# DINRELAY8.net
KiCad netlist of a schematic drawn in EAGLE
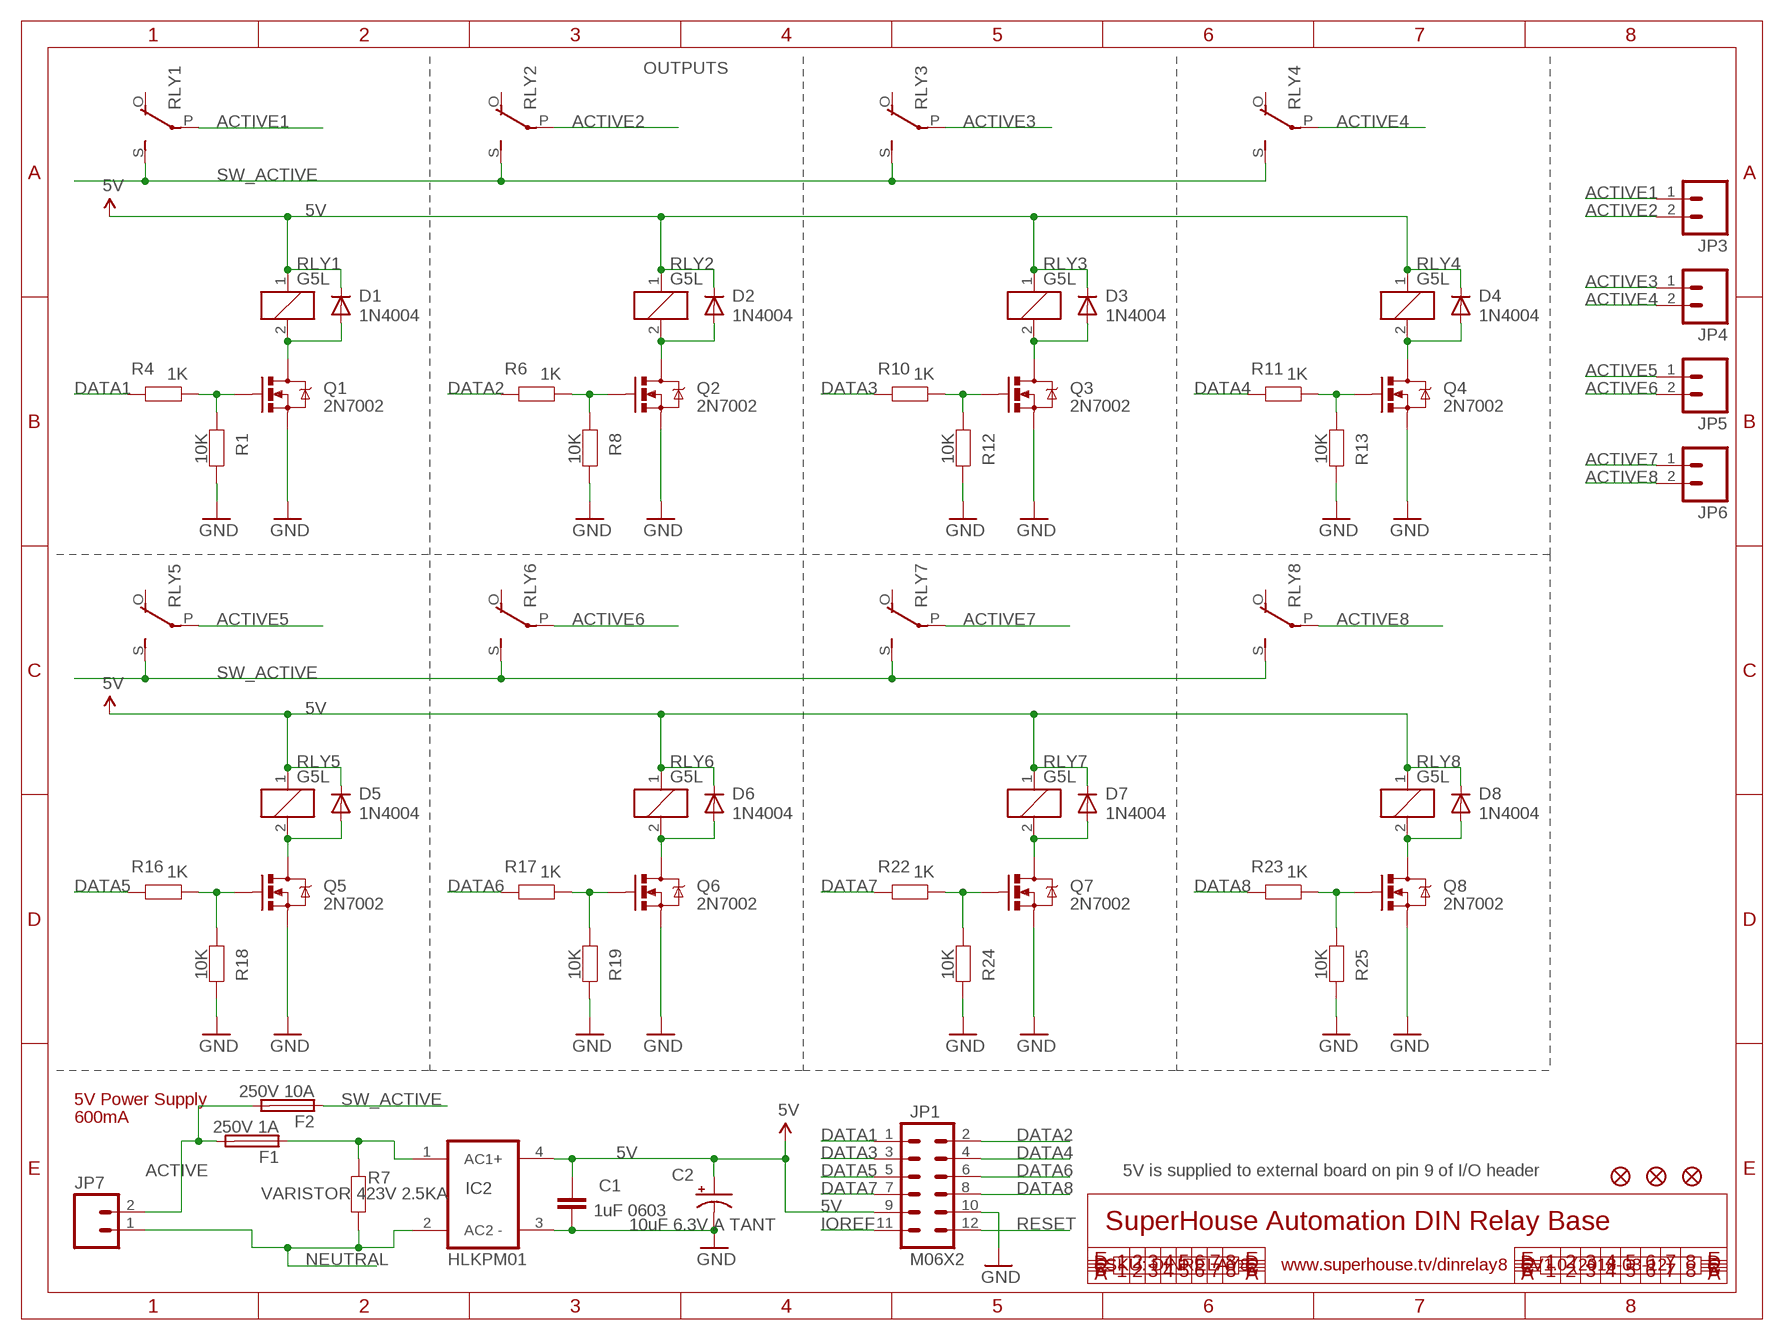
[diagram p0: schematic, sheet 1]

(export (version "E")
  (design (tool "Eeschema 10.0.6"))
  (components
    (comp (ref "C1")
      (value "1uF 0603")
      (footprint "eagle-import:0603@1")
      (libsource (lib "eagle-import") (part "CAP0603"))
    )
    (comp (ref "C2")
      (value "10uF 6.3V A TANT")
      (footprint "eagle-import:EIA3216")
      (libsource (lib "eagle-import") (part "CAP_POL1206"))
    )
    (comp (ref "D1")
      (value "1N4004")
      (footprint "eagle-import:SMB-DIODE")
      (libsource (lib "eagle-import") (part "DIODESMB"))
    )
    (comp (ref "D2")
      (value "1N4004")
      (footprint "eagle-import:SMB-DIODE")
      (libsource (lib "eagle-import") (part "DIODESMB"))
    )
    (comp (ref "D3")
      (value "1N4004")
      (footprint "eagle-import:SMB-DIODE")
      (libsource (lib "eagle-import") (part "DIODESMB"))
    )
    (comp (ref "D4")
      (value "1N4004")
      (footprint "eagle-import:SMB-DIODE")
      (libsource (lib "eagle-import") (part "DIODESMB"))
    )
    (comp (ref "D5")
      (value "1N4004")
      (footprint "eagle-import:SMB-DIODE")
      (libsource (lib "eagle-import") (part "DIODESMB"))
    )
    (comp (ref "D6")
      (value "1N4004")
      (footprint "eagle-import:SMB-DIODE")
      (libsource (lib "eagle-import") (part "DIODESMB"))
    )
    (comp (ref "D7")
      (value "1N4004")
      (footprint "eagle-import:SMB-DIODE")
      (libsource (lib "eagle-import") (part "DIODESMB"))
    )
    (comp (ref "D8")
      (value "1N4004")
      (footprint "eagle-import:SMB-DIODE")
      (libsource (lib "eagle-import") (part "DIODESMB"))
    )
    (comp (ref "F1")
      (value "250V 1A")
      (footprint "eagle-import:PICOFUSE")
      (libsource (lib "eagle-import") (part "PICOFUSEH"))
    )
    (comp (ref "F2")
      (value "250V 10A")
      (footprint "eagle-import:PICOFUSE")
      (libsource (lib "eagle-import") (part "PICOFUSEH"))
    )
    (comp (ref "FID1")
      (value "FIDUCIAL1X2.5")
      (footprint "eagle-import:FIDUCIAL-1X2.5")
      (libsource (lib "eagle-import") (part "FIDUCIAL1X2.5"))
    )
    (comp (ref "FID2")
      (value "FIDUCIAL1X2.5")
      (footprint "eagle-import:FIDUCIAL-1X2.5")
      (libsource (lib "eagle-import") (part "FIDUCIAL1X2.5"))
    )
    (comp (ref "FID3")
      (value "FIDUCIAL1X2.5")
      (footprint "eagle-import:FIDUCIAL-1X2.5")
      (libsource (lib "eagle-import") (part "FIDUCIAL1X2.5"))
    )
    (comp (ref "IC2")
      (value "HLKPM01")
      (footprint "eagle-import:HLKPM01")
      (libsource (lib "eagle-import") (part "HLKPM01"))
    )
    (comp (ref "JP1")
      (value "M06X2")
      (footprint "eagle-import:2X6-SHROUDED")
      (libsource (lib "eagle-import") (part "M06X2"))
    )
    (comp (ref "JP3")
      (value "M025MM")
      (footprint "eagle-import:SCREWTERMINAL-5MM-2")
      (libsource (lib "eagle-import") (part "M025MM"))
    )
    (comp (ref "JP4")
      (value "M025MM")
      (footprint "eagle-import:SCREWTERMINAL-5MM-2")
      (libsource (lib "eagle-import") (part "M025MM"))
    )
    (comp (ref "JP5")
      (value "M025MM")
      (footprint "eagle-import:SCREWTERMINAL-5MM-2")
      (libsource (lib "eagle-import") (part "M025MM"))
    )
    (comp (ref "JP6")
      (value "M025MM")
      (footprint "eagle-import:SCREWTERMINAL-5MM-2")
      (libsource (lib "eagle-import") (part "M025MM"))
    )
    (comp (ref "JP7")
      (value "M025MM")
      (footprint "eagle-import:SCREWTERMINAL-5MM-2")
      (libsource (lib "eagle-import") (part "M025MM"))
    )
    (comp (ref "Q1")
      (value "2N7002")
      (footprint "eagle-import:SOT23-3")
      (libsource (lib "eagle-import") (part "MOSFET-NCHANNELSMD"))
    )
    (comp (ref "Q2")
      (value "2N7002")
      (footprint "eagle-import:SOT23-3")
      (libsource (lib "eagle-import") (part "MOSFET-NCHANNELSMD"))
    )
    (comp (ref "Q3")
      (value "2N7002")
      (footprint "eagle-import:SOT23-3")
      (libsource (lib "eagle-import") (part "MOSFET-NCHANNELSMD"))
    )
    (comp (ref "Q4")
      (value "2N7002")
      (footprint "eagle-import:SOT23-3")
      (libsource (lib "eagle-import") (part "MOSFET-NCHANNELSMD"))
    )
    (comp (ref "Q5")
      (value "2N7002")
      (footprint "eagle-import:SOT23-3")
      (libsource (lib "eagle-import") (part "MOSFET-NCHANNELSMD"))
    )
    (comp (ref "Q6")
      (value "2N7002")
      (footprint "eagle-import:SOT23-3")
      (libsource (lib "eagle-import") (part "MOSFET-NCHANNELSMD"))
    )
    (comp (ref "Q7")
      (value "2N7002")
      (footprint "eagle-import:SOT23-3")
      (libsource (lib "eagle-import") (part "MOSFET-NCHANNELSMD"))
    )
    (comp (ref "Q8")
      (value "2N7002")
      (footprint "eagle-import:SOT23-3")
      (libsource (lib "eagle-import") (part "MOSFET-NCHANNELSMD"))
    )
    (comp (ref "R1")
      (value "10K")
      (footprint "eagle-import:0603")
      (libsource (lib "eagle-import") (part "RESISTOR0603"))
    )
    (comp (ref "R4")
      (value "1K")
      (footprint "eagle-import:0603")
      (libsource (lib "eagle-import") (part "RESISTOR0603"))
    )
    (comp (ref "R6")
      (value "1K")
      (footprint "eagle-import:0603")
      (libsource (lib "eagle-import") (part "RESISTOR0603"))
    )
    (comp (ref "R7")
      (value "VARISTOR 423V 2.5KA")
      (footprint "eagle-import:AXIAL-0.3")
      (libsource (lib "eagle-import") (part "freetronics-master-v1.1_RESISTORPTH1"))
    )
    (comp (ref "R8")
      (value "10K")
      (footprint "eagle-import:0603")
      (libsource (lib "eagle-import") (part "RESISTOR0603"))
    )
    (comp (ref "R10")
      (value "1K")
      (footprint "eagle-import:0603")
      (libsource (lib "eagle-import") (part "RESISTOR0603"))
    )
    (comp (ref "R11")
      (value "1K")
      (footprint "eagle-import:0603")
      (libsource (lib "eagle-import") (part "RESISTOR0603"))
    )
    (comp (ref "R12")
      (value "10K")
      (footprint "eagle-import:0603")
      (libsource (lib "eagle-import") (part "RESISTOR0603"))
    )
    (comp (ref "R13")
      (value "10K")
      (footprint "eagle-import:0603")
      (libsource (lib "eagle-import") (part "RESISTOR0603"))
    )
    (comp (ref "R16")
      (value "1K")
      (footprint "eagle-import:0603")
      (libsource (lib "eagle-import") (part "RESISTOR0603"))
    )
    (comp (ref "R17")
      (value "1K")
      (footprint "eagle-import:0603")
      (libsource (lib "eagle-import") (part "RESISTOR0603"))
    )
    (comp (ref "R18")
      (value "10K")
      (footprint "eagle-import:0603")
      (libsource (lib "eagle-import") (part "RESISTOR0603"))
    )
    (comp (ref "R19")
      (value "10K")
      (footprint "eagle-import:0603")
      (libsource (lib "eagle-import") (part "RESISTOR0603"))
    )
    (comp (ref "R22")
      (value "1K")
      (footprint "eagle-import:0603")
      (libsource (lib "eagle-import") (part "RESISTOR0603"))
    )
    (comp (ref "R23")
      (value "1K")
      (footprint "eagle-import:0603")
      (libsource (lib "eagle-import") (part "RESISTOR0603"))
    )
    (comp (ref "R24")
      (value "10K")
      (footprint "eagle-import:0603")
      (libsource (lib "eagle-import") (part "RESISTOR0603"))
    )
    (comp (ref "R25")
      (value "10K")
      (footprint "eagle-import:0603")
      (libsource (lib "eagle-import") (part "RESISTOR0603"))
    )
    (comp (ref "RLY1")
      (value "G5L")
      (footprint "eagle-import:G5LE")
      (libsource (lib "eagle-import") (part "G5L"))
    )
    (comp (ref "RLY2")
      (value "G5L")
      (footprint "eagle-import:G5LE")
      (libsource (lib "eagle-import") (part "G5L"))
    )
    (comp (ref "RLY3")
      (value "G5L")
      (footprint "eagle-import:G5LE")
      (libsource (lib "eagle-import") (part "G5L"))
    )
    (comp (ref "RLY4")
      (value "G5L")
      (footprint "eagle-import:G5LE")
      (libsource (lib "eagle-import") (part "G5L"))
    )
    (comp (ref "RLY5")
      (value "G5L")
      (footprint "eagle-import:G5LE")
      (libsource (lib "eagle-import") (part "G5L"))
    )
    (comp (ref "RLY6")
      (value "G5L")
      (footprint "eagle-import:G5LE")
      (libsource (lib "eagle-import") (part "G5L"))
    )
    (comp (ref "RLY7")
      (value "G5L")
      (footprint "eagle-import:G5LE")
      (libsource (lib "eagle-import") (part "G5L"))
    )
    (comp (ref "RLY8")
      (value "G5L")
      (footprint "eagle-import:G5LE")
      (libsource (lib "eagle-import") (part "G5L"))
    )
  )
  (nets
    (net (code "1") (name "/ACTIVE") (class "Default")
      (node (ref "F1") (pin "2") (pinfunction "2_2") (pintype "passive"))
      (node (ref "F2") (pin "2") (pinfunction "2_2") (pintype "passive"))
      (node (ref "JP7") (pin "2") (pinfunction "2_2") (pintype "passive"))
    )
    (net (code "2") (name "/ACTIVE1") (class "Default")
      (node (ref "JP3") (pin "1") (pinfunction "1_1") (pintype "passive"))
      (node (ref "RLY1") (pin "P") (pinfunction "P_P") (pintype "passive"))
    )
    (net (code "3") (name "/ACTIVE2") (class "Default")
      (node (ref "JP3") (pin "2") (pinfunction "2_2") (pintype "passive"))
      (node (ref "RLY2") (pin "P") (pinfunction "P_P") (pintype "passive"))
    )
    (net (code "4") (name "/ACTIVE3") (class "Default")
      (node (ref "JP4") (pin "1") (pinfunction "1_1") (pintype "passive"))
      (node (ref "RLY3") (pin "P") (pinfunction "P_P") (pintype "passive"))
    )
    (net (code "5") (name "/ACTIVE4") (class "Default")
      (node (ref "JP4") (pin "2") (pinfunction "2_2") (pintype "passive"))
      (node (ref "RLY4") (pin "P") (pinfunction "P_P") (pintype "passive"))
    )
    (net (code "6") (name "/ACTIVE5") (class "Default")
      (node (ref "JP5") (pin "1") (pinfunction "1_1") (pintype "passive"))
      (node (ref "RLY5") (pin "P") (pinfunction "P_P") (pintype "passive"))
    )
    (net (code "7") (name "/ACTIVE6") (class "Default")
      (node (ref "JP5") (pin "2") (pinfunction "2_2") (pintype "passive"))
      (node (ref "RLY6") (pin "P") (pinfunction "P_P") (pintype "passive"))
    )
    (net (code "8") (name "/ACTIVE7") (class "Default")
      (node (ref "JP6") (pin "1") (pinfunction "1_1") (pintype "passive"))
      (node (ref "RLY7") (pin "P") (pinfunction "P_P") (pintype "passive"))
    )
    (net (code "9") (name "/ACTIVE8") (class "Default")
      (node (ref "JP6") (pin "2") (pinfunction "2_2") (pintype "passive"))
      (node (ref "RLY8") (pin "P") (pinfunction "P_P") (pintype "passive"))
    )
    (net (code "10") (name "/DATA1") (class "Default")
      (node (ref "JP1") (pin "1") (pinfunction "1_1") (pintype "passive"))
      (node (ref "R4") (pin "2") (pinfunction "2_2") (pintype "passive"))
    )
    (net (code "11") (name "/DATA2") (class "Default")
      (node (ref "JP1") (pin "2") (pinfunction "2_2") (pintype "passive"))
      (node (ref "R6") (pin "2") (pinfunction "2_2") (pintype "passive"))
    )
    (net (code "12") (name "/DATA3") (class "Default")
      (node (ref "JP1") (pin "3") (pinfunction "3_3") (pintype "passive"))
      (node (ref "R10") (pin "2") (pinfunction "2_2") (pintype "passive"))
    )
    (net (code "13") (name "/DATA4") (class "Default")
      (node (ref "JP1") (pin "4") (pinfunction "4_4") (pintype "passive"))
      (node (ref "R11") (pin "2") (pinfunction "2_2") (pintype "passive"))
    )
    (net (code "14") (name "/DATA5") (class "Default")
      (node (ref "JP1") (pin "5") (pinfunction "5_5") (pintype "passive"))
      (node (ref "R16") (pin "2") (pinfunction "2_2") (pintype "passive"))
    )
    (net (code "15") (name "/DATA6") (class "Default")
      (node (ref "JP1") (pin "6") (pinfunction "6_6") (pintype "passive"))
      (node (ref "R17") (pin "2") (pinfunction "2_2") (pintype "passive"))
    )
    (net (code "16") (name "/DATA7") (class "Default")
      (node (ref "JP1") (pin "7") (pinfunction "7_7") (pintype "passive"))
      (node (ref "R22") (pin "2") (pinfunction "2_2") (pintype "passive"))
    )
    (net (code "17") (name "/DATA8") (class "Default")
      (node (ref "JP1") (pin "8") (pinfunction "8_8") (pintype "passive"))
      (node (ref "R23") (pin "2") (pinfunction "2_2") (pintype "passive"))
    )
    (net (code "18") (name "/IOREF") (class "Default")
      (node (ref "JP1") (pin "11") (pinfunction "11_11") (pintype "passive"))
    )
    (net (code "19") (name "/NEUTRAL") (class "Default")
      (node (ref "IC2") (pin "2") (pinfunction "AC2_2") (pintype "bidirectional"))
      (node (ref "JP7") (pin "1") (pinfunction "1_1") (pintype "passive"))
      (node (ref "R7") (pin "P$1") (pinfunction "1_P$1") (pintype "passive"))
    )
    (net (code "20") (name "/RESET") (class "Default")
      (node (ref "JP1") (pin "12") (pinfunction "12_12") (pintype "passive"))
    )
    (net (code "21") (name "/SW_ACTIVE") (class "Default")
      (node (ref "F2") (pin "1") (pinfunction "1_1") (pintype "passive"))
      (node (ref "RLY1") (pin "S") (pinfunction "S_S") (pintype "passive"))
      (node (ref "RLY2") (pin "S") (pinfunction "S_S") (pintype "passive"))
      (node (ref "RLY3") (pin "S") (pinfunction "S_S") (pintype "passive"))
      (node (ref "RLY4") (pin "S") (pinfunction "S_S") (pintype "passive"))
      (node (ref "RLY5") (pin "S") (pinfunction "S_S") (pintype "passive"))
      (node (ref "RLY6") (pin "S") (pinfunction "S_S") (pintype "passive"))
      (node (ref "RLY7") (pin "S") (pinfunction "S_S") (pintype "passive"))
      (node (ref "RLY8") (pin "S") (pinfunction "S_S") (pintype "passive"))
    )
    (net (code "22") (name "5V") (class "Default")
      (node (ref "C1") (pin "1") (pinfunction "1_1") (pintype "passive"))
      (node (ref "C2") (pin "A") (pinfunction "+_A") (pintype "passive"))
      (node (ref "D1") (pin "C") (pinfunction "C_C") (pintype "passive"))
      (node (ref "D2") (pin "C") (pinfunction "C_C") (pintype "passive"))
      (node (ref "D3") (pin "C") (pinfunction "C_C") (pintype "passive"))
      (node (ref "D4") (pin "C") (pinfunction "C_C") (pintype "passive"))
      (node (ref "D5") (pin "C") (pinfunction "C_C") (pintype "passive"))
      (node (ref "D6") (pin "C") (pinfunction "C_C") (pintype "passive"))
      (node (ref "D7") (pin "C") (pinfunction "C_C") (pintype "passive"))
      (node (ref "D8") (pin "C") (pinfunction "C_C") (pintype "passive"))
      (node (ref "IC2") (pin "4") (pinfunction "+_4") (pintype "bidirectional"))
      (node (ref "JP1") (pin "9") (pinfunction "9_9") (pintype "passive"))
      (node (ref "RLY1") (pin "1") (pinfunction "1_1") (pintype "passive"))
      (node (ref "RLY2") (pin "1") (pinfunction "1_1") (pintype "passive"))
      (node (ref "RLY3") (pin "1") (pinfunction "1_1") (pintype "passive"))
      (node (ref "RLY4") (pin "1") (pinfunction "1_1") (pintype "passive"))
      (node (ref "RLY5") (pin "1") (pinfunction "1_1") (pintype "passive"))
      (node (ref "RLY6") (pin "1") (pinfunction "1_1") (pintype "passive"))
      (node (ref "RLY7") (pin "1") (pinfunction "1_1") (pintype "passive"))
      (node (ref "RLY8") (pin "1") (pinfunction "1_1") (pintype "passive"))
    )
    (net (code "23") (name "GND") (class "Default")
      (node (ref "C1") (pin "2") (pinfunction "2_2") (pintype "passive"))
      (node (ref "C2") (pin "C") (pinfunction "-_C") (pintype "passive"))
      (node (ref "IC2") (pin "3") (pinfunction "-_3") (pintype "bidirectional"))
      (node (ref "JP1") (pin "10") (pinfunction "10_10") (pintype "passive"))
      (node (ref "Q1") (pin "2") (pinfunction "S_2") (pintype "passive"))
      (node (ref "Q2") (pin "2") (pinfunction "S_2") (pintype "passive"))
      (node (ref "Q3") (pin "2") (pinfunction "S_2") (pintype "passive"))
      (node (ref "Q4") (pin "2") (pinfunction "S_2") (pintype "passive"))
      (node (ref "Q5") (pin "2") (pinfunction "S_2") (pintype "passive"))
      (node (ref "Q6") (pin "2") (pinfunction "S_2") (pintype "passive"))
      (node (ref "Q7") (pin "2") (pinfunction "S_2") (pintype "passive"))
      (node (ref "Q8") (pin "2") (pinfunction "S_2") (pintype "passive"))
      (node (ref "R1") (pin "2") (pinfunction "2_2") (pintype "passive"))
      (node (ref "R12") (pin "2") (pinfunction "2_2") (pintype "passive"))
      (node (ref "R13") (pin "2") (pinfunction "2_2") (pintype "passive"))
      (node (ref "R18") (pin "2") (pinfunction "2_2") (pintype "passive"))
      (node (ref "R19") (pin "2") (pinfunction "2_2") (pintype "passive"))
      (node (ref "R24") (pin "2") (pinfunction "2_2") (pintype "passive"))
      (node (ref "R25") (pin "2") (pinfunction "2_2") (pintype "passive"))
      (node (ref "R8") (pin "2") (pinfunction "2_2") (pintype "passive"))
    )
    (net (code "24") (name "Net-(IC2-AC1)") (class "Default")
      (node (ref "F1") (pin "1") (pinfunction "1_1") (pintype "passive"))
      (node (ref "IC2") (pin "1") (pinfunction "AC1_1") (pintype "bidirectional"))
      (node (ref "R7") (pin "P$2") (pinfunction "2_P$2") (pintype "passive"))
    )
    (net (code "25") (name "Net-(Q1-D)") (class "Default")
      (node (ref "D1") (pin "A") (pinfunction "A_A") (pintype "passive"))
      (node (ref "Q1") (pin "3") (pinfunction "D_3") (pintype "passive"))
      (node (ref "RLY1") (pin "2") (pinfunction "2_2") (pintype "passive"))
    )
    (net (code "26") (name "Net-(Q1-G)") (class "Default")
      (node (ref "Q1") (pin "1") (pinfunction "G_1") (pintype "passive"))
      (node (ref "R1") (pin "1") (pinfunction "1_1") (pintype "passive"))
      (node (ref "R4") (pin "1") (pinfunction "1_1") (pintype "passive"))
    )
    (net (code "27") (name "Net-(Q2-D)") (class "Default")
      (node (ref "D2") (pin "A") (pinfunction "A_A") (pintype "passive"))
      (node (ref "Q2") (pin "3") (pinfunction "D_3") (pintype "passive"))
      (node (ref "RLY2") (pin "2") (pinfunction "2_2") (pintype "passive"))
    )
    (net (code "28") (name "Net-(Q2-G)") (class "Default")
      (node (ref "Q2") (pin "1") (pinfunction "G_1") (pintype "passive"))
      (node (ref "R6") (pin "1") (pinfunction "1_1") (pintype "passive"))
      (node (ref "R8") (pin "1") (pinfunction "1_1") (pintype "passive"))
    )
    (net (code "29") (name "Net-(Q3-D)") (class "Default")
      (node (ref "D3") (pin "A") (pinfunction "A_A") (pintype "passive"))
      (node (ref "Q3") (pin "3") (pinfunction "D_3") (pintype "passive"))
      (node (ref "RLY3") (pin "2") (pinfunction "2_2") (pintype "passive"))
    )
    (net (code "30") (name "Net-(Q3-G)") (class "Default")
      (node (ref "Q3") (pin "1") (pinfunction "G_1") (pintype "passive"))
      (node (ref "R10") (pin "1") (pinfunction "1_1") (pintype "passive"))
      (node (ref "R12") (pin "1") (pinfunction "1_1") (pintype "passive"))
    )
    (net (code "31") (name "Net-(Q4-D)") (class "Default")
      (node (ref "D4") (pin "A") (pinfunction "A_A") (pintype "passive"))
      (node (ref "Q4") (pin "3") (pinfunction "D_3") (pintype "passive"))
      (node (ref "RLY4") (pin "2") (pinfunction "2_2") (pintype "passive"))
    )
    (net (code "32") (name "Net-(Q4-G)") (class "Default")
      (node (ref "Q4") (pin "1") (pinfunction "G_1") (pintype "passive"))
      (node (ref "R11") (pin "1") (pinfunction "1_1") (pintype "passive"))
      (node (ref "R13") (pin "1") (pinfunction "1_1") (pintype "passive"))
    )
    (net (code "33") (name "Net-(Q5-D)") (class "Default")
      (node (ref "D5") (pin "A") (pinfunction "A_A") (pintype "passive"))
      (node (ref "Q5") (pin "3") (pinfunction "D_3") (pintype "passive"))
      (node (ref "RLY5") (pin "2") (pinfunction "2_2") (pintype "passive"))
    )
    (net (code "34") (name "Net-(Q5-G)") (class "Default")
      (node (ref "Q5") (pin "1") (pinfunction "G_1") (pintype "passive"))
      (node (ref "R16") (pin "1") (pinfunction "1_1") (pintype "passive"))
      (node (ref "R18") (pin "1") (pinfunction "1_1") (pintype "passive"))
    )
    (net (code "35") (name "Net-(Q6-D)") (class "Default")
      (node (ref "D6") (pin "A") (pinfunction "A_A") (pintype "passive"))
      (node (ref "Q6") (pin "3") (pinfunction "D_3") (pintype "passive"))
      (node (ref "RLY6") (pin "2") (pinfunction "2_2") (pintype "passive"))
    )
    (net (code "36") (name "Net-(Q6-G)") (class "Default")
      (node (ref "Q6") (pin "1") (pinfunction "G_1") (pintype "passive"))
      (node (ref "R17") (pin "1") (pinfunction "1_1") (pintype "passive"))
      (node (ref "R19") (pin "1") (pinfunction "1_1") (pintype "passive"))
    )
    (net (code "37") (name "Net-(Q7-D)") (class "Default")
      (node (ref "D7") (pin "A") (pinfunction "A_A") (pintype "passive"))
      (node (ref "Q7") (pin "3") (pinfunction "D_3") (pintype "passive"))
      (node (ref "RLY7") (pin "2") (pinfunction "2_2") (pintype "passive"))
    )
    (net (code "38") (name "Net-(Q7-G)") (class "Default")
      (node (ref "Q7") (pin "1") (pinfunction "G_1") (pintype "passive"))
      (node (ref "R22") (pin "1") (pinfunction "1_1") (pintype "passive"))
      (node (ref "R24") (pin "1") (pinfunction "1_1") (pintype "passive"))
    )
    (net (code "39") (name "Net-(Q8-D)") (class "Default")
      (node (ref "D8") (pin "A") (pinfunction "A_A") (pintype "passive"))
      (node (ref "Q8") (pin "3") (pinfunction "D_3") (pintype "passive"))
      (node (ref "RLY8") (pin "2") (pinfunction "2_2") (pintype "passive"))
    )
    (net (code "40") (name "Net-(Q8-G)") (class "Default")
      (node (ref "Q8") (pin "1") (pinfunction "G_1") (pintype "passive"))
      (node (ref "R23") (pin "1") (pinfunction "1_1") (pintype "passive"))
      (node (ref "R25") (pin "1") (pinfunction "1_1") (pintype "passive"))
    )
    (net (code "41") (name "unconnected-(RLY1-PadO)") (class "Default")
      (node (ref "RLY1") (pin "O") (pinfunction "O_O") (pintype "passive"))
    )
    (net (code "42") (name "unconnected-(RLY2-PadO)") (class "Default")
      (node (ref "RLY2") (pin "O") (pinfunction "O_O") (pintype "passive"))
    )
    (net (code "43") (name "unconnected-(RLY3-PadO)") (class "Default")
      (node (ref "RLY3") (pin "O") (pinfunction "O_O") (pintype "passive"))
    )
    (net (code "44") (name "unconnected-(RLY4-PadO)") (class "Default")
      (node (ref "RLY4") (pin "O") (pinfunction "O_O") (pintype "passive"))
    )
    (net (code "45") (name "unconnected-(RLY5-PadO)") (class "Default")
      (node (ref "RLY5") (pin "O") (pinfunction "O_O") (pintype "passive"))
    )
    (net (code "46") (name "unconnected-(RLY6-PadO)") (class "Default")
      (node (ref "RLY6") (pin "O") (pinfunction "O_O") (pintype "passive"))
    )
    (net (code "47") (name "unconnected-(RLY7-PadO)") (class "Default")
      (node (ref "RLY7") (pin "O") (pinfunction "O_O") (pintype "passive"))
    )
    (net (code "48") (name "unconnected-(RLY8-PadO)") (class "Default")
      (node (ref "RLY8") (pin "O") (pinfunction "O_O") (pintype "passive"))
    )
  )
)
